# Sheet1.net
KiCad netlist of a schematic drawn in Altium Designer
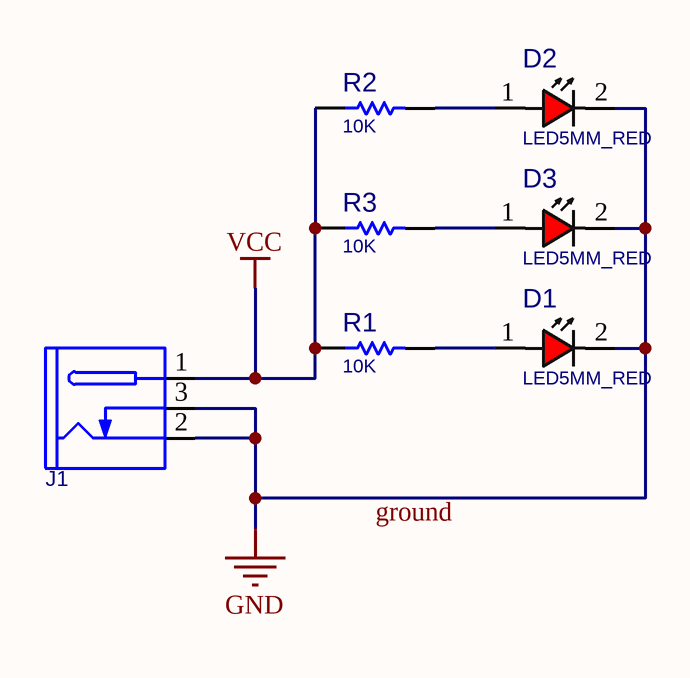
[diagram p0: Sheet1.SchDoc]

(export (version "E")
  (design (tool "Eeschema 10.0.6"))
  (components
    (comp (ref "D1")
      (value "LED5MM_RED")
      (footprint "LED5MM_RED")
      (description "LED, THD, 5MM, RED")
      (fields (field (name "MANF") "MANF") (field (name "MANF_P#") "MANF_PART#"))
      (libsource (lib "led(diode)") (part "LED_THD_5MM_RED"))
    )
    (comp (ref "D2")
      (value "LED5MM_RED")
      (footprint "LED5MM_RED")
      (description "LED, THD, 5MM, RED")
      (fields (field (name "MANF") "MANF") (field (name "MANF_P#") "MANF_PART#"))
      (libsource (lib "led(diode)") (part "LED_THD_5MM_RED"))
    )
    (comp (ref "D3")
      (value "LED5MM_RED")
      (footprint "LED5MM_RED")
      (description "LED, THD, 5MM, RED")
      (fields (field (name "MANF") "MANF") (field (name "MANF_P#") "MANF_PART#"))
      (libsource (lib "led(diode)") (part "LED_THD_5MM_RED"))
    )
    (comp (ref "J1")
      (value "DC_POWER_JACK")
      (footprint "JAC_PWR1")
      (description "CONN, PWR JACK DC, PLUG DIAM 1.0MM RA THD")
      (fields (field (name "MANF") "CUI STACK") (field (name "MANF_P#") "PJ-031CH, PJ-031C"))
      (libsource (lib "conn_powerJack") (part "CONN_PWR_JACKR1"))
    )
    (comp (ref "R1")
      (value "10K")
      (footprint "R025W_AX04")
      (description "RESISTOR, THD")
      (fields (field (name "MANF_P#") "RK73H1ETTP4701F") (field (name "MANF") "KOA SPEER"))
      (libsource (lib "passive_thd") (part "RES_THD"))
    )
    (comp (ref "R2")
      (value "10K")
      (footprint "R025W_AX04")
      (description "RESISTOR, THD")
      (fields (field (name "MANF_P#") "RK73H1ETTP4701F") (field (name "MANF") "KOA SPEER"))
      (libsource (lib "passive_thd") (part "RES_THD"))
    )
    (comp (ref "R3")
      (value "10K")
      (footprint "R025W_AX04")
      (description "RESISTOR, THD")
      (fields (field (name "MANF_P#") "RK73H1ETTP4701F") (field (name "MANF") "KOA SPEER"))
      (libsource (lib "passive_thd") (part "RES_THD"))
    )
  )
  (nets
    (net (code "2") (name "GND") (class "Default")
      (node (ref "D1") (pin "2") (pinfunction "CATHODE_2") (pintype "passive"))
      (node (ref "D2") (pin "2") (pinfunction "CATHODE_2") (pintype "passive"))
      (node (ref "D3") (pin "2") (pinfunction "CATHODE_2") (pintype "passive"))
      (node (ref "J1") (pin "2") (pinfunction "SLEEVE_2") (pintype "power_in"))
      (node (ref "J1") (pin "3") (pinfunction "INSERTION_DET_3") (pintype "power_in"))
    )
    (net (code "3") (name "Net-(D1-ANODE)") (class "Default")
      (node (ref "D1") (pin "1") (pinfunction "ANODE_1") (pintype "passive"))
      (node (ref "R1") (pin "2") (pinfunction "2_2") (pintype "passive"))
    )
    (net (code "4") (name "Net-(D2-ANODE)") (class "Default")
      (node (ref "D2") (pin "1") (pinfunction "ANODE_1") (pintype "passive"))
      (node (ref "R2") (pin "2") (pinfunction "2_2") (pintype "passive"))
    )
    (net (code "5") (name "Net-(D3-ANODE)") (class "Default")
      (node (ref "D3") (pin "1") (pinfunction "ANODE_1") (pintype "passive"))
      (node (ref "R3") (pin "2") (pinfunction "2_2") (pintype "passive"))
    )
    (net (code "6") (name "VCC") (class "Default")
      (node (ref "J1") (pin "1") (pinfunction "TIP_1") (pintype "power_in"))
      (node (ref "R1") (pin "1") (pinfunction "1_1") (pintype "passive"))
      (node (ref "R2") (pin "1") (pinfunction "1_1") (pintype "passive"))
      (node (ref "R3") (pin "1") (pinfunction "1_1") (pintype "passive"))
    )
  )
)
